# Trans.net
KiCad netlist of a schematic drawn in Altium Designer
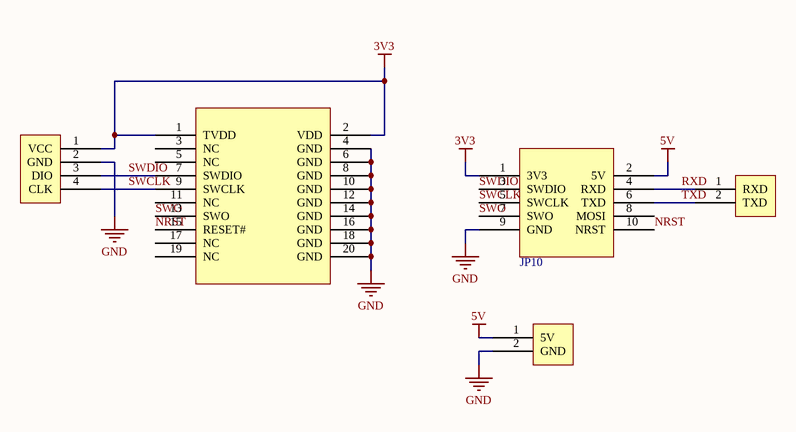
[diagram p0: Trans.SchDoc]

(export (version "E")
  (design (tool "Eeschema 10.0.6"))
  (components
    (comp (ref "J3") (value "JP2") (footprint "2Pin") (libsource (lib "Schlib1") (part "JP2")))
    (comp (ref "J10Pin") (value "JP10") (footprint "10P") (libsource (lib "Schlib1") (part "JP10")))
    (comp (ref "JTAG") (value "JP20") (footprint "20P") (libsource (lib "Schlib1") (part "JP20")))
    (comp (ref "Pow") (value "Pow5V") (footprint "2Pin") (libsource (lib "Schlib1") (part "Pow5V")))
    (comp (ref "SW") (value "JP4") (footprint "4Pin") (libsource (lib "Schlib1") (part "JP4")))
  )
  (nets
    (net (code "1") (name "/NRST") (class "Default")
      (node (ref "J10Pin") (pin "10") (pinfunction "NRST_10") (pintype "passive"))
      (node (ref "JTAG") (pin "15") (pinfunction "RESET#_15") (pintype "passive"))
    )
    (net (code "2") (name "/RXD") (class "Default")
      (node (ref "J10Pin") (pin "4") (pinfunction "RXD_4") (pintype "passive"))
      (node (ref "J3") (pin "1") (pinfunction "RXD_1") (pintype "passive"))
    )
    (net (code "3") (name "/SWCLK") (class "Default")
      (node (ref "J10Pin") (pin "5") (pinfunction "SWCLK_5") (pintype "passive"))
      (node (ref "JTAG") (pin "9") (pinfunction "SWCLK_9") (pintype "passive"))
      (node (ref "SW") (pin "4") (pinfunction "CLK_4") (pintype "passive"))
    )
    (net (code "4") (name "/SWDIO") (class "Default")
      (node (ref "J10Pin") (pin "3") (pinfunction "SWDIO_3") (pintype "passive"))
      (node (ref "JTAG") (pin "7") (pinfunction "SWDIO_7") (pintype "passive"))
      (node (ref "SW") (pin "3") (pinfunction "DIO_3") (pintype "passive"))
    )
    (net (code "5") (name "/SWO") (class "Default")
      (node (ref "J10Pin") (pin "7") (pinfunction "SWO_7") (pintype "passive"))
      (node (ref "JTAG") (pin "13") (pinfunction "SWO_13") (pintype "passive"))
    )
    (net (code "6") (name "/TXD") (class "Default")
      (node (ref "J10Pin") (pin "6") (pinfunction "TXD_6") (pintype "passive"))
      (node (ref "J3") (pin "2") (pinfunction "TXD_2") (pintype "passive"))
    )
    (net (code "7") (name "3V3") (class "Default")
      (node (ref "J10Pin") (pin "1") (pinfunction "3V3_1") (pintype "passive"))
      (node (ref "JTAG") (pin "1") (pinfunction "TVDD_1") (pintype "passive"))
      (node (ref "JTAG") (pin "2") (pinfunction "VDD_2") (pintype "passive"))
      (node (ref "SW") (pin "1") (pinfunction "VCC_1") (pintype "passive"))
    )
    (net (code "8") (name "5V") (class "Default")
      (node (ref "J10Pin") (pin "2") (pinfunction "5V_2") (pintype "passive"))
      (node (ref "Pow") (pin "1") (pinfunction "5V_1") (pintype "passive"))
    )
    (net (code "9") (name "GND") (class "Default")
      (node (ref "J10Pin") (pin "9") (pinfunction "GND_9") (pintype "passive"))
      (node (ref "JTAG") (pin "10") (pinfunction "GND_10") (pintype "passive"))
      (node (ref "JTAG") (pin "12") (pinfunction "GND_12") (pintype "passive"))
      (node (ref "JTAG") (pin "14") (pinfunction "GND_14") (pintype "passive"))
      (node (ref "JTAG") (pin "16") (pinfunction "GND_16") (pintype "passive"))
      (node (ref "JTAG") (pin "18") (pinfunction "GND_18") (pintype "passive"))
      (node (ref "JTAG") (pin "20") (pinfunction "GND_20") (pintype "passive"))
      (node (ref "JTAG") (pin "4") (pinfunction "GND_4") (pintype "passive"))
      (node (ref "JTAG") (pin "6") (pinfunction "GND_6") (pintype "passive"))
      (node (ref "JTAG") (pin "8") (pinfunction "GND_8") (pintype "passive"))
      (node (ref "Pow") (pin "2") (pinfunction "GND_2") (pintype "passive"))
      (node (ref "SW") (pin "2") (pinfunction "GND_2") (pintype "passive"))
    )
    (net (code "10") (name "unconnected-(J10Pin-MOSI-Pad8)") (class "Default")
      (node (ref "J10Pin") (pin "8") (pinfunction "MOSI_8") (pintype "passive"))
    )
    (net (code "11") (name "unconnected-(JTAG-NC-Pad3)") (class "Default")
      (node (ref "JTAG") (pin "3") (pinfunction "NC_3") (pintype "passive"))
    )
    (net (code "12") (name "unconnected-(JTAG-NC-Pad5)") (class "Default")
      (node (ref "JTAG") (pin "5") (pinfunction "NC_5") (pintype "passive"))
    )
    (net (code "13") (name "unconnected-(JTAG-NC-Pad11)") (class "Default")
      (node (ref "JTAG") (pin "11") (pinfunction "NC_11") (pintype "passive"))
    )
    (net (code "14") (name "unconnected-(JTAG-NC-Pad17)") (class "Default")
      (node (ref "JTAG") (pin "17") (pinfunction "NC_17") (pintype "passive"))
    )
    (net (code "15") (name "unconnected-(JTAG-NC-Pad19)") (class "Default")
      (node (ref "JTAG") (pin "19") (pinfunction "NC_19") (pintype "passive"))
    )
  )
)
